# DE-010824.net
KiCad netlist of a schematic drawn in Altium Designer
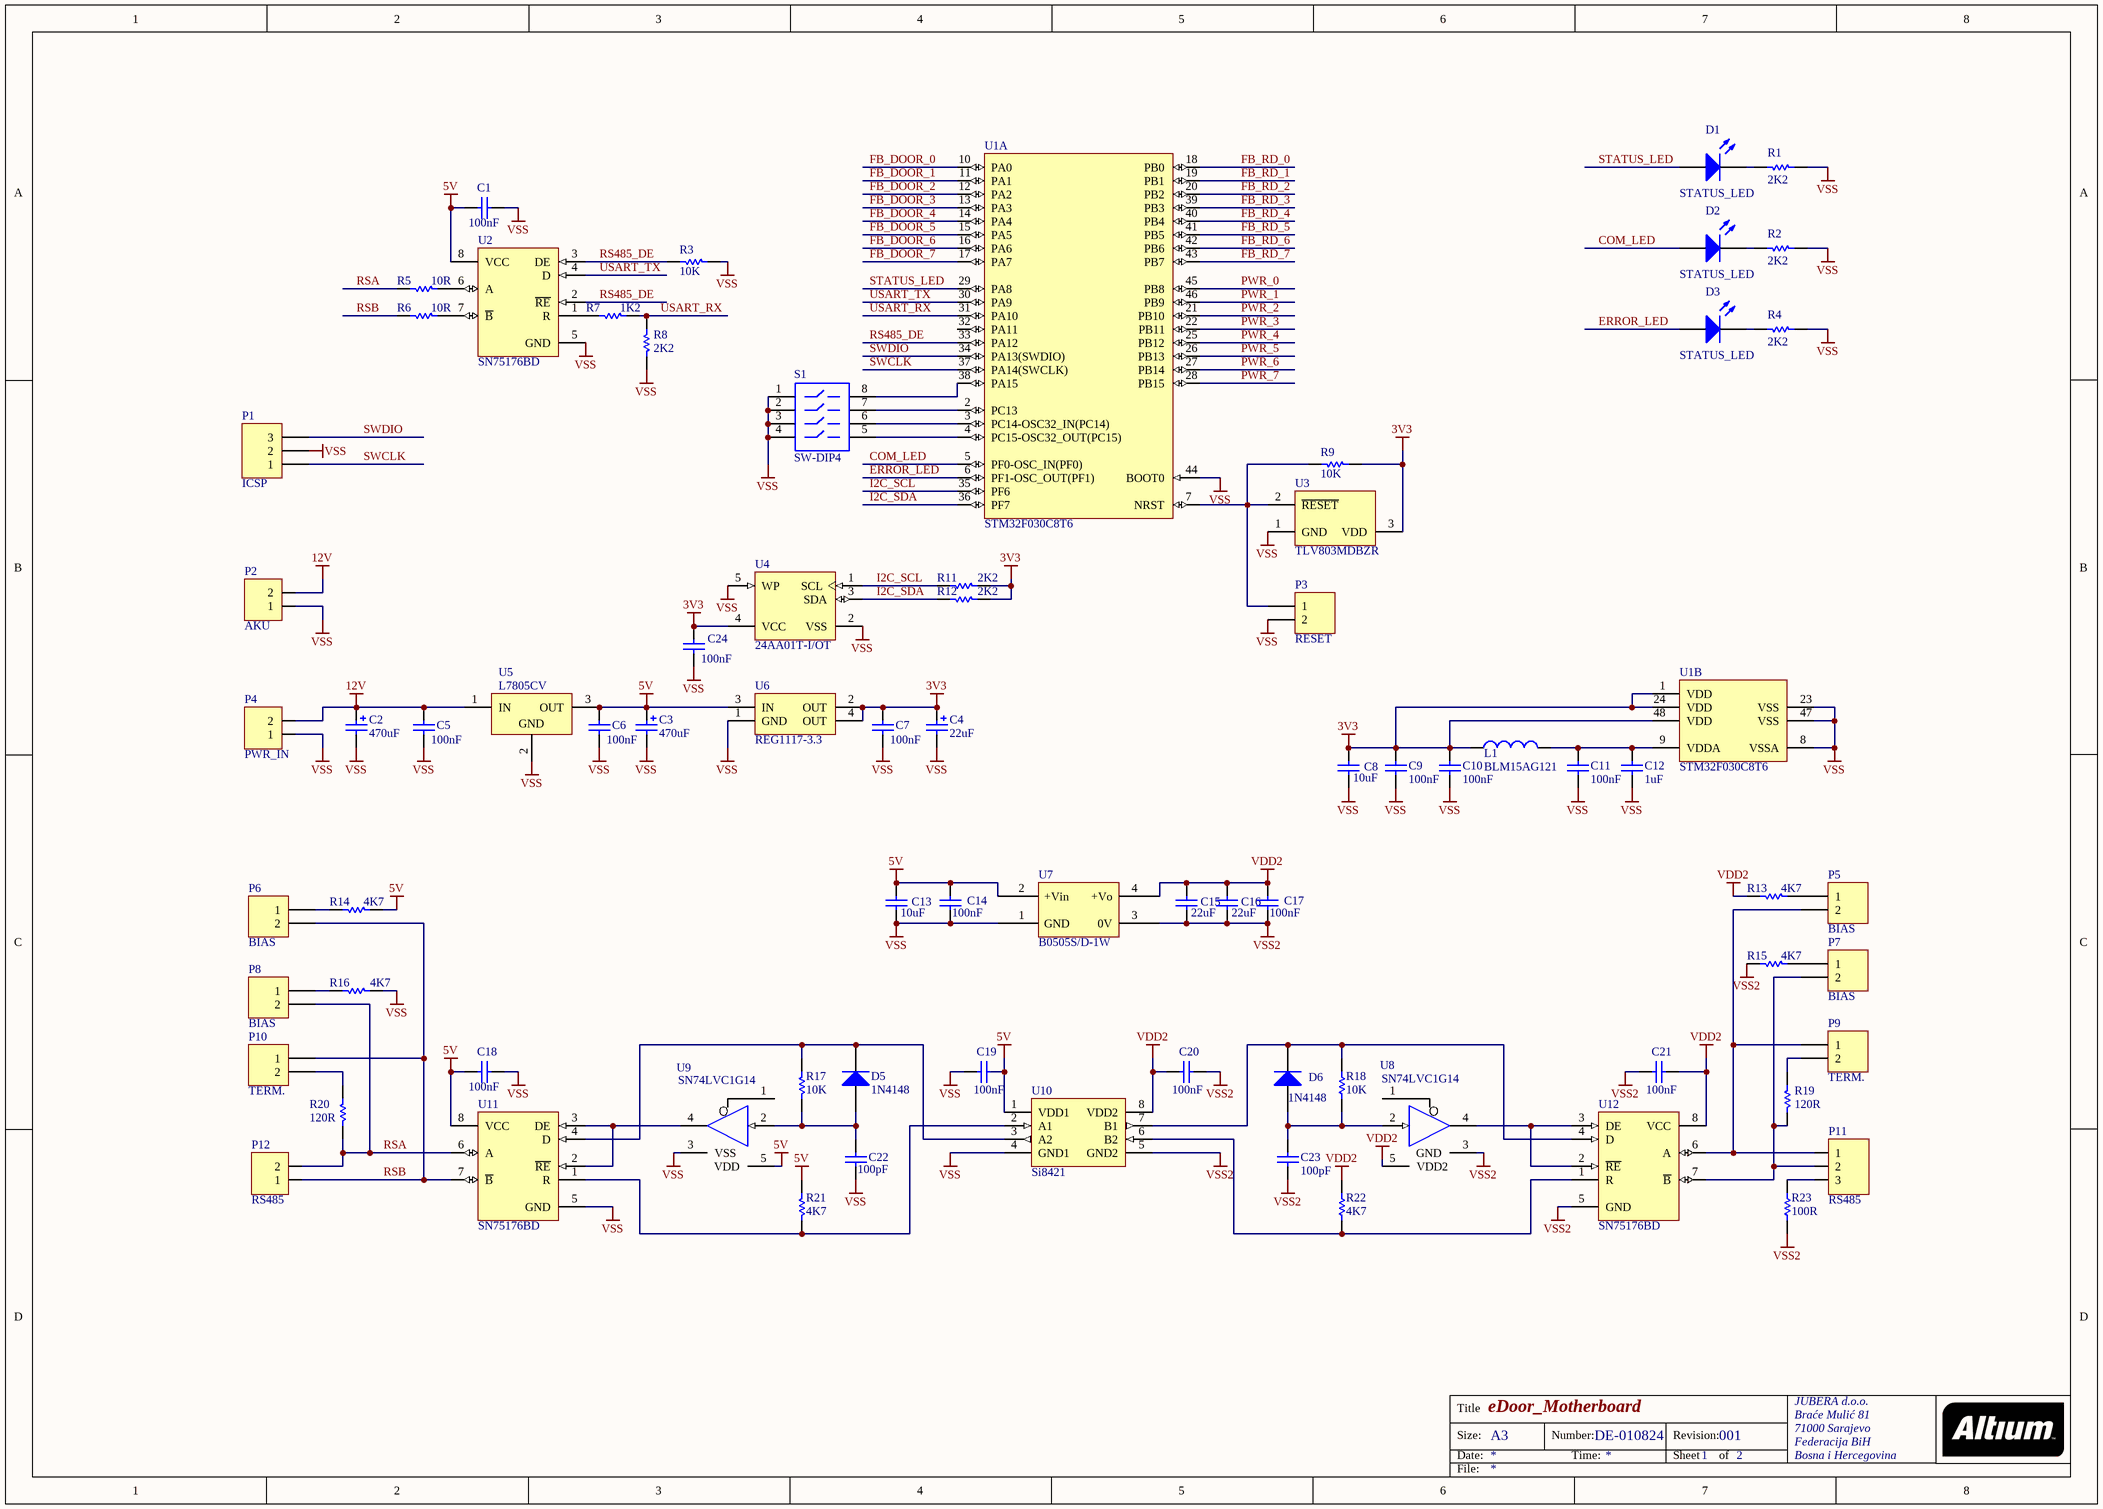
[diagram p0: DE-010824.SchDoc]

(export (version "E")
  (design (tool "Eeschema 10.0.6"))
  (components
    (comp (ref "C1")
      (value "100nF")
      (footprint "0603")
      (description "Ceramic Chip Capacitor - Standard")
      (fields (field (name "PUBLISHER") "Altium Limited"))
      (libsource (lib "DE-220817") (part "C0603"))
    )
    (comp (ref "C2")
      (value "470uF")
      (footprint "CAPPR5-10X12.5")
      (description "Aluminum Electrolytic Capacitor, Radial Style with Long Leads: 470uF, 25V")
      (fields (field (name "PUBLISHER") "Altium Limited"))
      (libsource (lib "DE-010824") (part "EKA00DC347E00"))
    )
    (comp (ref "C3")
      (value "470uF")
      (footprint "CAPPR5-10X12.5")
      (description "Aluminum Electrolytic Capacitor, Radial Style with Long Leads: 470uF, 25V")
      (fields (field (name "PUBLISHER") "Altium Limited"))
      (libsource (lib "DE-010824") (part "EKA00DC347E00"))
    )
    (comp (ref "C4")
      (value "22uF")
      (footprint "CAPPR2-5X11")
      (description "Aluminum Electrolytic Capacitor, Radial Style with Long Leads: 47uF, 35V")
      (fields (field (name "PUBLISHER") "Altium Limited"))
      (libsource (lib "DE-010824") (part "EKA00AA247F00"))
    )
    (comp (ref "C5")
      (value "100nF")
      (footprint "0603")
      (description "Ceramic Chip Capacitor - Standard")
      (fields (field (name "PUBLISHER") "Altium Limited"))
      (libsource (lib "DE-220817") (part "C0603"))
    )
    (comp (ref "C6")
      (value "100nF")
      (footprint "0603")
      (description "Ceramic Chip Capacitor - Standard")
      (fields (field (name "PUBLISHER") "Altium Limited"))
      (libsource (lib "DE-220817") (part "C0603"))
    )
    (comp (ref "C7")
      (value "100nF")
      (footprint "0603")
      (description "Ceramic Chip Capacitor - Standard")
      (fields (field (name "PUBLISHER") "Altium Limited"))
      (libsource (lib "DE-220817") (part "C0603"))
    )
    (comp (ref "C8")
      (value "10uF")
      (footprint "0805")
      (description "Ceramic Chip Capacitor - Standard")
      (fields (field (name "PUBLISHER") "Altium Limited"))
      (libsource (lib "DE-220817") (part "C0805"))
    )
    (comp (ref "C9")
      (value "100nF")
      (footprint "0603")
      (description "Ceramic Chip Capacitor - Standard")
      (fields (field (name "PUBLISHER") "Altium Limited"))
      (libsource (lib "DE-220817") (part "C0603"))
    )
    (comp (ref "C10")
      (value "100nF")
      (footprint "0603")
      (description "Ceramic Chip Capacitor - Standard")
      (fields (field (name "PUBLISHER") "Altium Limited"))
      (libsource (lib "DE-220817") (part "C0603"))
    )
    (comp (ref "C11")
      (value "100nF")
      (footprint "0603")
      (description "Ceramic Chip Capacitor - Standard")
      (fields (field (name "PUBLISHER") "Altium Limited"))
      (libsource (lib "DE-220817") (part "C0603"))
    )
    (comp (ref "C12")
      (value "1uF")
      (footprint "0603")
      (description "Ceramic Chip Capacitor - Standard")
      (fields (field (name "PUBLISHER") "Altium Limited"))
      (libsource (lib "DE-220817") (part "C0603"))
    )
    (comp (ref "C13")
      (value "10uF")
      (footprint "0805")
      (description "Ceramic Chip Capacitor - Standard")
      (fields (field (name "PUBLISHER") "Altium Limited"))
      (libsource (lib "DE-220817") (part "C0805"))
    )
    (comp (ref "C14")
      (value "100nF")
      (footprint "0603")
      (description "Ceramic Chip Capacitor - Standard")
      (fields (field (name "PUBLISHER") "Altium Limited"))
      (libsource (lib "DE-220817") (part "C0603"))
    )
    (comp (ref "C15")
      (value "22uF")
      (footprint "0805")
      (description "Ceramic Chip Capacitor - Standard")
      (fields (field (name "PUBLISHER") "Altium Limited"))
      (libsource (lib "DE-220817") (part "C0805"))
    )
    (comp (ref "C16")
      (value "22uF")
      (footprint "0805")
      (description "Ceramic Chip Capacitor - Standard")
      (fields (field (name "PUBLISHER") "Altium Limited"))
      (libsource (lib "DE-220817") (part "C0805"))
    )
    (comp (ref "C17")
      (value "100nF")
      (footprint "0603")
      (description "Ceramic Chip Capacitor - Standard")
      (fields (field (name "PUBLISHER") "Altium Limited"))
      (libsource (lib "DE-220817") (part "C0603"))
    )
    (comp (ref "C18")
      (value "100nF")
      (footprint "0603")
      (description "Ceramic Chip Capacitor - Standard")
      (fields (field (name "PUBLISHER") "Altium Limited"))
      (libsource (lib "DE-220817") (part "C0603"))
    )
    (comp (ref "C19")
      (value "100nF")
      (footprint "0603")
      (description "Ceramic Chip Capacitor - Standard")
      (fields (field (name "PUBLISHER") "Altium Limited"))
      (libsource (lib "DE-220817") (part "C0603"))
    )
    (comp (ref "C20")
      (value "100nF")
      (footprint "0603")
      (description "Ceramic Chip Capacitor - Standard")
      (fields (field (name "PUBLISHER") "Altium Limited"))
      (libsource (lib "DE-220817") (part "C0603"))
    )
    (comp (ref "C21")
      (value "100nF")
      (footprint "0603")
      (description "Ceramic Chip Capacitor - Standard")
      (fields (field (name "PUBLISHER") "Altium Limited"))
      (libsource (lib "DE-220817") (part "C0603"))
    )
    (comp (ref "C22")
      (value "100pF")
      (footprint "0603")
      (description "Ceramic Chip Capacitor - Standard")
      (fields (field (name "PUBLISHER") "Altium Limited"))
      (libsource (lib "DE-220817") (part "C0603"))
    )
    (comp (ref "C23")
      (value "100pF")
      (footprint "0603")
      (description "Ceramic Chip Capacitor - Standard")
      (fields (field (name "PUBLISHER") "Altium Limited"))
      (libsource (lib "DE-220817") (part "C0603"))
    )
    (comp (ref "C24")
      (value "100nF")
      (footprint "0603")
      (description "Ceramic Chip Capacitor - Standard")
      (fields (field (name "PUBLISHER") "Altium Limited"))
      (libsource (lib "DE-220817") (part "C0603"))
    )
    (comp (ref "D1")
      (value "STATUS_LED")
      (footprint "1.6X0.8X0.8")
      (description "Blue Surface Mount Chip LED, Blue")
      (fields (field (name "PUBLISHER") "Altium Limited"))
      (libsource (lib "DE-010824") (part "HSMB-C190"))
    )
    (comp (ref "D2")
      (value "STATUS_LED")
      (footprint "1.6X0.8X0.8")
      (description "Blue Surface Mount Chip LED, Blue")
      (fields (field (name "PUBLISHER") "Altium Limited"))
      (libsource (lib "DE-010824") (part "HSMB-C190"))
    )
    (comp (ref "D3")
      (value "STATUS_LED")
      (footprint "1.6X0.8X0.8")
      (description "Blue Surface Mount Chip LED, Blue")
      (fields (field (name "PUBLISHER") "Altium Limited"))
      (libsource (lib "DE-010824") (part "HSMB-C190"))
    )
    (comp (ref "D5")
      (value "1N4148")
      (footprint "SOD323")
      (description "General-purpose Diode")
      (fields (field (name "PUBLISHER") "Altium Limited"))
      (libsource (lib "Philips Discrete Diode - Switching") (part "BAS321"))
    )
    (comp (ref "D6")
      (value "1N4148")
      (footprint "SOD323")
      (description "General-purpose Diode")
      (fields (field (name "PUBLISHER") "Altium Limited"))
      (libsource (lib "Philips Discrete Diode - Switching") (part "BAS321"))
    )
    (comp (ref "L1")
      (value "BLM15AG121")
      (footprint "0603")
      (description "SMD chip inductor")
      (fields (field (name "PUBLISHER") "Altium Limited"))
      (libsource (lib "DE-010824") (part "Chip inductor"))
    )
    (comp (ref "P1")
      (value "ICSP")
      (footprint "HDR1X3")
      (description "Header, 3-Pin")
      (fields (field (name "PUBLISHER") "Altium Limited"))
      (libsource (lib "Miscellaneous Connectors") (part "Header 3"))
    )
    (comp (ref "P2")
      (value "AKU")
      (footprint "TERMINAL BLOK 2")
      (description "Terminal blok konektor 3,5 mm")
      (libsource (lib "DE-010824") (part "TERMINAL BLOK 2"))
    )
    (comp (ref "P3")
      (value "RESET")
      (footprint "HDR1X2")
      (description "Header, 2-Pin")
      (fields (field (name "PUBLISHER") "Altium Limited"))
      (libsource (lib "Miscellaneous Connectors") (part "Header 2"))
    )
    (comp (ref "P4")
      (value "PWR_IN")
      (footprint "TERMINAL BLOK 2")
      (description "Terminal blok konektor 3,5 mm")
      (libsource (lib "DE-010824") (part "TERMINAL BLOK 2"))
    )
    (comp (ref "P5")
      (value "BIAS")
      (footprint "HDR1X2")
      (description "Header, 2-Pin")
      (fields (field (name "PUBLISHER") "Altium Limited"))
      (libsource (lib "Miscellaneous Connectors") (part "Header 2"))
    )
    (comp (ref "P6")
      (value "BIAS")
      (footprint "HDR1X2")
      (description "Header, 2-Pin")
      (fields (field (name "PUBLISHER") "Altium Limited"))
      (libsource (lib "") (part "Header 2_1"))
    )
    (comp (ref "P7")
      (value "BIAS")
      (footprint "HDR1X2")
      (description "Header, 2-Pin")
      (fields (field (name "PUBLISHER") "Altium Limited"))
      (libsource (lib "Miscellaneous Connectors") (part "Header 2"))
    )
    (comp (ref "P8")
      (value "BIAS")
      (footprint "HDR1X2")
      (description "Header, 2-Pin")
      (fields (field (name "PUBLISHER") "Altium Limited"))
      (libsource (lib "") (part "Header 2_1"))
    )
    (comp (ref "P9")
      (value "TERM.")
      (footprint "HDR1X2")
      (description "Header, 2-Pin")
      (fields (field (name "PUBLISHER") "Altium Limited"))
      (libsource (lib "Miscellaneous Connectors") (part "Header 2"))
    )
    (comp (ref "P10")
      (value "TERM.")
      (footprint "HDR1X2")
      (description "Header, 2-Pin")
      (fields (field (name "PUBLISHER") "Altium Limited"))
      (libsource (lib "") (part "Header 2_1"))
    )
    (comp (ref "P11")
      (value "RS485")
      (footprint "TERMINAL BLOK 3")
      (description "3 pinski terminal blok konektor")
      (libsource (lib "DE-010824") (part "TERMINAL BLOK 3"))
    )
    (comp (ref "P12")
      (value "RS485")
      (footprint "TERMINAL BLOK 2")
      (description "Terminal blok konektor 3,5 mm")
      (libsource (lib "DE-010824") (part "TERMINAL BLOK 2"))
    )
    (comp (ref "R1")
      (value "2K2")
      (footprint "ERA-0603")
      (fields (field (name "PUBLISHER") "Altium Limited"))
      (libsource (lib "DE-220817") (part "ERAV"))
    )
    (comp (ref "R2")
      (value "2K2")
      (footprint "ERA-0603")
      (fields (field (name "PUBLISHER") "Altium Limited"))
      (libsource (lib "DE-220817") (part "ERAV"))
    )
    (comp (ref "R3")
      (value "10K")
      (footprint "ERA-0603")
      (fields (field (name "PUBLISHER") "Altium Limited"))
      (libsource (lib "DE-220817") (part "ERAV"))
    )
    (comp (ref "R4")
      (value "2K2")
      (footprint "ERA-0603")
      (fields (field (name "PUBLISHER") "Altium Limited"))
      (libsource (lib "DE-220817") (part "ERAV"))
    )
    (comp (ref "R5")
      (value "10R")
      (footprint "ERA-0603")
      (fields (field (name "PUBLISHER") "Altium Limited"))
      (libsource (lib "DE-220817") (part "ERAV"))
    )
    (comp (ref "R6")
      (value "10R")
      (footprint "ERA-0603")
      (fields (field (name "PUBLISHER") "Altium Limited"))
      (libsource (lib "DE-220817") (part "ERAV"))
    )
    (comp (ref "R7")
      (value "1K2")
      (footprint "ERA-0603")
      (fields (field (name "PUBLISHER") "Altium Limited"))
      (libsource (lib "DE-220817") (part "ERAV"))
    )
    (comp (ref "R8")
      (value "2K2")
      (footprint "ERA-0603")
      (fields (field (name "PUBLISHER") "Altium Limited"))
      (libsource (lib "DE-220817") (part "ERAV"))
    )
    (comp (ref "R9")
      (value "10K")
      (footprint "ERA-0603")
      (fields (field (name "PUBLISHER") "Altium Limited"))
      (libsource (lib "DE-220817") (part "ERAV"))
    )
    (comp (ref "R11")
      (value "2K2")
      (footprint "ERA-0603")
      (fields (field (name "PUBLISHER") "Altium Limited"))
      (libsource (lib "DE-220817") (part "ERAV"))
    )
    (comp (ref "R12")
      (value "2K2")
      (footprint "ERA-0603")
      (fields (field (name "PUBLISHER") "Altium Limited"))
      (libsource (lib "DE-220817") (part "ERAV"))
    )
    (comp (ref "R13")
      (value "4K7")
      (footprint "ERA-0603")
      (fields (field (name "PUBLISHER") "Altium Limited"))
      (libsource (lib "DE-220817") (part "ERAV"))
    )
    (comp (ref "R14")
      (value "4K7")
      (footprint "ERA-0603")
      (fields (field (name "PUBLISHER") "Altium Limited"))
      (libsource (lib "DE-220817") (part "ERAV"))
    )
    (comp (ref "R15")
      (value "4K7")
      (footprint "ERA-0603")
      (fields (field (name "PUBLISHER") "Altium Limited"))
      (libsource (lib "DE-220817") (part "ERAV"))
    )
    (comp (ref "R16")
      (value "4K7")
      (footprint "ERA-0603")
      (fields (field (name "PUBLISHER") "Altium Limited"))
      (libsource (lib "DE-220817") (part "ERAV"))
    )
    (comp (ref "R17")
      (value "10K")
      (footprint "ERA-0603")
      (fields (field (name "PUBLISHER") "Altium Limited"))
      (libsource (lib "DE-220817") (part "ERAV"))
    )
    (comp (ref "R18")
      (value "10K")
      (footprint "ERA-0603")
      (fields (field (name "PUBLISHER") "Altium Limited"))
      (libsource (lib "DE-220817") (part "ERAV"))
    )
    (comp (ref "R19")
      (value "120R")
      (footprint "ERA-0603")
      (fields (field (name "PUBLISHER") "Altium Limited"))
      (libsource (lib "DE-220817") (part "ERAV"))
    )
    (comp (ref "R20")
      (value "120R")
      (footprint "ERA-0603")
      (fields (field (name "PUBLISHER") "Altium Limited"))
      (libsource (lib "DE-220817") (part "ERAV"))
    )
    (comp (ref "R21")
      (value "4K7")
      (footprint "ERA-0603")
      (fields (field (name "PUBLISHER") "Altium Limited"))
      (libsource (lib "DE-220817") (part "ERAV"))
    )
    (comp (ref "R22")
      (value "4K7")
      (footprint "ERA-0603")
      (fields (field (name "PUBLISHER") "Altium Limited"))
      (libsource (lib "DE-220817") (part "ERAV"))
    )
    (comp (ref "R23")
      (value "100R")
      (footprint "ERA-0805")
      (fields (field (name "PUBLISHER") "Altium Limited"))
      (libsource (lib "DE-010824") (part "ERA6Y"))
    )
    (comp (ref "S1")
      (value "SW-DIP4")
      (footprint "DIP-8")
      (description "DIP Switch")
      (fields (field (name "PUBLISHER") "Altium Limited"))
      (libsource (lib "Miscellaneous Devices") (part "SW-DIP4"))
    )
    (comp (ref "U1")
      (value "STM32F030C8T6")
      (footprint "STM-LQFP48_N")
      (libsource (lib "STMicroelectronics STM32 F0") (part "STM32F030C8T6"))
    )
    (comp (ref "U2")
      (value "SN75176BD")
      (footprint "D008_N")
      (description "Differential Bus Transceiver")
      (fields (field (name "PUBLISHER") "Altium Limited"))
      (libsource (lib "DE-010824") (part "SN75176BD"))
    )
    (comp (ref "U3")
      (value "TLV803MDBZR")
      (footprint "DBZ3_N")
      (fields (field (name "MANUFACTURER") "Texas Instruments"))
      (libsource (lib "TI Power Management Supervisor and Reset IC") (part "TLV803MDBZR"))
    )
    (comp (ref "U4")
      (value "24AA01T-I/OT")
      (footprint "SOT-23-OT5_N")
      (description "1Kbit, 400kHz, 1.8V, I2C Serial EEPROM, 5-Pin SOT-23, Industrial Temperature, Tape and Reel")
      (fields (field (name "PUBLISHER") "Altium Limited"))
      (libsource (lib "Microchip Memory I2C Serial EEPROM") (part "24AA01T-I/OT"))
    )
    (comp (ref "U5")
      (value "L7805CV")
      (footprint "TO220")
      (description "Positive Voltage Regulator, 5V, 3-Pin TO-220")
      (libsource (lib "DE-010824") (part "L7805CV"))
    )
    (comp (ref "U6")
      (value "REG1117-3.3")
      (footprint "ZZ311")
      (description "800mA and 1A Low Dropout Positive Regulator 2.85V, 3.3V, 5V, and Adjustable")
      (fields (field (name "PUBLISHER") "Altium Limited"))
      (libsource (lib "DE-010824") (part "REG1117-3.3"))
    )
    (comp (ref "U7")
      (value "B0505S/D-1W")
      (footprint "B0505S-1W")
      (description "1W isolated dc dc converter")
      (libsource (lib "DE-220817") (part "B0505S/D"))
    )
    (comp (ref "U8")
      (value "SN74LVC1G14")
      (footprint "419A-01_N")
      (description "Non-Inverting 3-State Buffer")
      (fields (field (name "PUBLISHER") "Altium Limited"))
      (libsource (lib "ON Semi Logic Buffer Line Driver") (part "MC74VHC1G125DFT1"))
    )
    (comp (ref "U9")
      (value "SN74LVC1G14")
      (footprint "419A-01_N")
      (description "Non-Inverting 3-State Buffer")
      (fields (field (name "PUBLISHER") "Altium Limited"))
      (libsource (lib "ON Semi Logic Buffer Line Driver") (part "MC74VHC1G125DFT1"))
    )
    (comp (ref "U10")
      (value "Si8421")
      (footprint "SOP8")
      (description "Silicon Labs low power dual chanel digital isolator")
      (libsource (lib "DE-010824") (part "Si8421"))
    )
    (comp (ref "U11")
      (value "SN75176BD")
      (footprint "D008_N")
      (description "Differential Bus Transceiver")
      (fields (field (name "PUBLISHER") "Altium Limited"))
      (libsource (lib "") (part "SN75176BD_1"))
    )
    (comp (ref "U12")
      (value "SN75176BD")
      (footprint "D008_N")
      (description "Differential Bus Transceiver")
      (fields (field (name "PUBLISHER") "Altium Limited"))
      (libsource (lib "DE-220817") (part "SN75176BD"))
    )
  )
  (nets
    (net (code "1") (name "/COM_LED") (class "Default")
      (node (ref "D2") (pin "1") (pinfunction "A_1") (pintype "passive"))
      (node (ref "U1") (pin "5") (pinfunction "PF0-OSC_IN(PF0)_5") (pintype "bidirectional"))
    )
    (net (code "2") (name "/ERROR_LED") (class "Default")
      (node (ref "D3") (pin "1") (pinfunction "A_1") (pintype "passive"))
      (node (ref "U1") (pin "6") (pinfunction "PF1-OSC_OUT(PF1)_6") (pintype "bidirectional"))
    )
    (net (code "3") (name "/FB_DOOR_0") (class "Default")
      (node (ref "U1") (pin "10") (pinfunction "PA0_10") (pintype "bidirectional"))
    )
    (net (code "4") (name "/FB_DOOR_1") (class "Default")
      (node (ref "U1") (pin "11") (pinfunction "PA1_11") (pintype "bidirectional"))
    )
    (net (code "5") (name "/FB_DOOR_2") (class "Default")
      (node (ref "U1") (pin "12") (pinfunction "PA2_12") (pintype "bidirectional"))
    )
    (net (code "6") (name "/FB_DOOR_3") (class "Default")
      (node (ref "U1") (pin "13") (pinfunction "PA3_13") (pintype "bidirectional"))
    )
    (net (code "7") (name "/FB_DOOR_4") (class "Default")
      (node (ref "U1") (pin "14") (pinfunction "PA4_14") (pintype "bidirectional"))
    )
    (net (code "8") (name "/FB_DOOR_5") (class "Default")
      (node (ref "U1") (pin "15") (pinfunction "PA5_15") (pintype "bidirectional"))
    )
    (net (code "9") (name "/FB_DOOR_6") (class "Default")
      (node (ref "U1") (pin "16") (pinfunction "PA6_16") (pintype "bidirectional"))
    )
    (net (code "10") (name "/FB_DOOR_7") (class "Default")
      (node (ref "U1") (pin "17") (pinfunction "PA7_17") (pintype "bidirectional"))
    )
    (net (code "11") (name "/FB_RD_0") (class "Default")
      (node (ref "U1") (pin "18") (pinfunction "PB0_18") (pintype "bidirectional"))
    )
    (net (code "12") (name "/FB_RD_1") (class "Default")
      (node (ref "U1") (pin "19") (pinfunction "PB1_19") (pintype "bidirectional"))
    )
    (net (code "13") (name "/FB_RD_2") (class "Default")
      (node (ref "U1") (pin "20") (pinfunction "PB2_20") (pintype "bidirectional"))
    )
    (net (code "14") (name "/FB_RD_3") (class "Default")
      (node (ref "U1") (pin "39") (pinfunction "PB3_39") (pintype "bidirectional"))
    )
    (net (code "15") (name "/FB_RD_4") (class "Default")
      (node (ref "U1") (pin "40") (pinfunction "PB4_40") (pintype "bidirectional"))
    )
    (net (code "16") (name "/FB_RD_5") (class "Default")
      (node (ref "U1") (pin "41") (pinfunction "PB5_41") (pintype "bidirectional"))
    )
    (net (code "17") (name "/FB_RD_6") (class "Default")
      (node (ref "U1") (pin "42") (pinfunction "PB6_42") (pintype "bidirectional"))
    )
    (net (code "18") (name "/FB_RD_7") (class "Default")
      (node (ref "U1") (pin "43") (pinfunction "PB7_43") (pintype "bidirectional"))
    )
    (net (code "19") (name "/I2C_SCL") (class "Default")
      (node (ref "R11") (pin "1") (pinfunction "1_1") (pintype "passive"))
      (node (ref "U1") (pin "35") (pinfunction "PF6_35") (pintype "bidirectional"))
      (node (ref "U4") (pin "1") (pinfunction "SCL_1") (pintype "input"))
    )
    (net (code "20") (name "/I2C_SDA") (class "Default")
      (node (ref "R12") (pin "1") (pinfunction "1_1") (pintype "passive"))
      (node (ref "U1") (pin "36") (pinfunction "PF7_36") (pintype "bidirectional"))
      (node (ref "U4") (pin "3") (pinfunction "SDA_3") (pintype "bidirectional"))
    )
    (net (code "21") (name "/PWR_0") (class "Default")
      (node (ref "U1") (pin "45") (pinfunction "PB8_45") (pintype "bidirectional"))
    )
    (net (code "22") (name "/PWR_1") (class "Default")
      (node (ref "U1") (pin "46") (pinfunction "PB9_46") (pintype "bidirectional"))
    )
    (net (code "23") (name "/PWR_2") (class "Default")
      (node (ref "U1") (pin "21") (pinfunction "PB10_21") (pintype "bidirectional"))
    )
    (net (code "24") (name "/PWR_3") (class "Default")
      (node (ref "U1") (pin "22") (pinfunction "PB11_22") (pintype "bidirectional"))
    )
    (net (code "25") (name "/PWR_4") (class "Default")
      (node (ref "U1") (pin "25") (pinfunction "PB12_25") (pintype "bidirectional"))
    )
    (net (code "26") (name "/PWR_5") (class "Default")
      (node (ref "U1") (pin "26") (pinfunction "PB13_26") (pintype "bidirectional"))
    )
    (net (code "27") (name "/PWR_6") (class "Default")
      (node (ref "U1") (pin "27") (pinfunction "PB14_27") (pintype "bidirectional"))
    )
    (net (code "28") (name "/PWR_7") (class "Default")
      (node (ref "U1") (pin "28") (pinfunction "PB15_28") (pintype "bidirectional"))
    )
    (net (code "29") (name "/RS485_DE") (class "Default")
      (node (ref "R3") (pin "2") (pinfunction "2_2") (pintype "passive"))
      (node (ref "U1") (pin "33") (pinfunction "PA12_33") (pintype "bidirectional"))
      (node (ref "U2") (pin "2") (pinfunction "~{RE}_2") (pintype "input"))
      (node (ref "U2") (pin "3") (pinfunction "DE_3") (pintype "input"))
    )
    (net (code "30") (name "/RSA") (class "Default")
      (node (ref "P12") (pin "2") (pinfunction "2_2") (pintype "passive"))
      (node (ref "P8") (pin "2") (pinfunction "2_2") (pintype "passive"))
      (node (ref "R20") (pin "1") (pinfunction "1_1") (pintype "passive"))
      (node (ref "R5") (pin "1") (pinfunction "1_1") (pintype "passive"))
      (node (ref "U11") (pin "6") (pinfunction "A_6") (pintype "bidirectional"))
    )
    (net (code "31") (name "/RSB") (class "Default")
      (node (ref "P10") (pin "1") (pinfunction "1_1") (pintype "passive"))
      (node (ref "P12") (pin "1") (pinfunction "1_1") (pintype "passive"))
      (node (ref "P6") (pin "2") (pinfunction "2_2") (pintype "passive"))
      (node (ref "R6") (pin "1") (pinfunction "1_1") (pintype "passive"))
      (node (ref "U11") (pin "7") (pinfunction "~{B}_7") (pintype "bidirectional"))
    )
    (net (code "32") (name "/STATUS_LED") (class "Default")
      (node (ref "D1") (pin "1") (pinfunction "A_1") (pintype "passive"))
      (node (ref "U1") (pin "29") (pinfunction "PA8_29") (pintype "bidirectional"))
    )
    (net (code "33") (name "/SWCLK") (class "Default")
      (node (ref "P1") (pin "1") (pinfunction "1_1") (pintype "passive"))
      (node (ref "U1") (pin "37") (pinfunction "PA14(SWCLK)_37") (pintype "bidirectional"))
    )
    (net (code "34") (name "/SWDIO") (class "Default")
      (node (ref "P1") (pin "3") (pinfunction "3_3") (pintype "passive"))
      (node (ref "U1") (pin "34") (pinfunction "PA13(SWDIO)_34") (pintype "bidirectional"))
    )
    (net (code "35") (name "/USART_RX") (class "Default")
      (node (ref "R7") (pin "1") (pinfunction "1_1") (pintype "passive"))
      (node (ref "R8") (pin "1") (pinfunction "1_1") (pintype "passive"))
      (node (ref "U1") (pin "31") (pinfunction "PA10_31") (pintype "bidirectional"))
    )
    (net (code "36") (name "/USART_TX") (class "Default")
      (node (ref "U1") (pin "30") (pinfunction "PA9_30") (pintype "bidirectional"))
      (node (ref "U2") (pin "4") (pinfunction "D_4") (pintype "input"))
    )
    (net (code "37") (name "3V3") (class "Default")
      (node (ref "C10") (pin "1") (pinfunction "1_1") (pintype "passive"))
      (node (ref "C24") (pin "2") (pinfunction "2_2") (pintype "passive"))
      (node (ref "C4") (pin "1") (pinfunction "1_1") (pintype "passive"))
      (node (ref "C7") (pin "2") (pinfunction "2_2") (pintype "passive"))
      (node (ref "C8") (pin "2") (pinfunction "2_2") (pintype "passive"))
      (node (ref "C9") (pin "1") (pinfunction "1_1") (pintype "passive"))
      (node (ref "L1") (pin "1") (pinfunction "1_1") (pintype "passive"))
      (node (ref "R11") (pin "2") (pinfunction "2_2") (pintype "passive"))
      (node (ref "R12") (pin "2") (pinfunction "2_2") (pintype "passive"))
      (node (ref "R9") (pin "2") (pinfunction "2_2") (pintype "passive"))
      (node (ref "U1") (pin "1") (pinfunction "VDD_1") (pintype "power_in"))
      (node (ref "U1") (pin "24") (pinfunction "VDD_24") (pintype "power_in"))
      (node (ref "U1") (pin "48") (pinfunction "VDD_48") (pintype "power_in"))
      (node (ref "U3") (pin "3") (pinfunction "VDD_3") (pintype "power_in"))
      (node (ref "U4") (pin "4") (pinfunction "VCC_4") (pintype "power_in"))
      (node (ref "U6") (pin "2") (pinfunction "OUT_2") (pintype "power_in"))
      (node (ref "U6") (pin "4") (pinfunction "OUT_4") (pintype "power_in"))
    )
    (net (code "38") (name "5V") (class "Default")
      (node (ref "C1") (pin "1") (pinfunction "1_1") (pintype "passive"))
      (node (ref "C13") (pin "2") (pinfunction "2_2") (pintype "passive"))
      (node (ref "C14") (pin "2") (pinfunction "2_2") (pintype "passive"))
      (node (ref "C15") (pin "2") (pinfunction "2_2") (pintype "passive"))
      (node (ref "C16") (pin "2") (pinfunction "2_2") (pintype "passive"))
      (node (ref "C17") (pin "2") (pinfunction "2_2") (pintype "passive"))
      (node (ref "C18") (pin "1") (pinfunction "1_1") (pintype "passive"))
      (node (ref "C19") (pin "2") (pinfunction "2_2") (pintype "passive"))
      (node (ref "C20") (pin "2") (pinfunction "2_2") (pintype "passive"))
      (node (ref "C21") (pin "1") (pinfunction "1_1") (pintype "passive"))
      (node (ref "C3") (pin "1") (pinfunction "1_1") (pintype "passive"))
      (node (ref "C6") (pin "2") (pinfunction "2_2") (pintype "passive"))
      (node (ref "R13") (pin "2") (pinfunction "2_2") (pintype "passive"))
      (node (ref "R14") (pin "2") (pinfunction "2_2") (pintype "passive"))
      (node (ref "R21") (pin "2") (pinfunction "2_2") (pintype "passive"))
      (node (ref "R22") (pin "2") (pinfunction "2_2") (pintype "passive"))
      (node (ref "U10") (pin "1") (pinfunction "VDD1_1") (pintype "power_in"))
      (node (ref "U10") (pin "8") (pinfunction "VDD2_8") (pintype "power_in"))
      (node (ref "U11") (pin "8") (pinfunction "VCC_8") (pintype "power_in"))
      (node (ref "U12") (pin "8") (pinfunction "VCC_8") (pintype "power_in"))
      (node (ref "U2") (pin "8") (pinfunction "VCC_8") (pintype "power_in"))
      (node (ref "U5") (pin "3") (pinfunction "OUT_3") (pintype "power_in"))
      (node (ref "U6") (pin "3") (pinfunction "IN_3") (pintype "power_in"))
      (node (ref "U7") (pin "2") (pinfunction "+Vin_2") (pintype "passive"))
      (node (ref "U7") (pin "4") (pinfunction "+Vo_4") (pintype "passive"))
      (node (ref "U8") (pin "5") (pinfunction "VDD2_5") (pintype "power_in"))
      (node (ref "U9") (pin "5") (pinfunction "VDD2_5") (pintype "power_in"))
    )
    (net (code "39") (name "12V") (class "Default")
      (node (ref "C2") (pin "1") (pinfunction "1_1") (pintype "passive"))
      (node (ref "C5") (pin "2") (pinfunction "2_2") (pintype "passive"))
      (node (ref "P2") (pin "2") (pinfunction "2_2") (pintype "passive"))
      (node (ref "P4") (pin "2") (pinfunction "2_2") (pintype "passive"))
      (node (ref "U5") (pin "1") (pinfunction "IN_1") (pintype "power_in"))
    )
    (net (code "40") (name "Net-(D1-K)") (class "Default")
      (node (ref "D1") (pin "2") (pinfunction "K_2") (pintype "passive"))
      (node (ref "R1") (pin "2") (pinfunction "2_2") (pintype "passive"))
    )
    (net (code "41") (name "Net-(D2-K)") (class "Default")
      (node (ref "D2") (pin "2") (pinfunction "K_2") (pintype "passive"))
      (node (ref "R2") (pin "2") (pinfunction "2_2") (pintype "passive"))
    )
    (net (code "42") (name "Net-(D3-K)") (class "Default")
      (node (ref "D3") (pin "2") (pinfunction "K_2") (pintype "passive"))
      (node (ref "R4") (pin "2") (pinfunction "2_2") (pintype "passive"))
    )
    (net (code "43") (name "Net-(D5-A)") (class "Default")
      (node (ref "C22") (pin "2") (pinfunction "2_2") (pintype "passive"))
      (node (ref "D5") (pin "2") (pinfunction "A_2") (pintype "passive"))
      (node (ref "R17") (pin "1") (pinfunction "1_1") (pintype "passive"))
      (node (ref "U9") (pin "2") (pinfunction "A_2") (pintype "input"))
    )
    (net (code "44") (name "Net-(D5-K)") (class "Default")
      (node (ref "D5") (pin "1") (pinfunction "K_1") (pintype "passive"))
      (node (ref "R17") (pin "2") (pinfunction "2_2") (pintype "passive"))
      (node (ref "U10") (pin "3") (pinfunction "A2_3") (pintype "output"))
      (node (ref "U11") (pin "4") (pinfunction "D_4") (pintype "input"))
    )
    (net (code "45") (name "Net-(D6-A)") (class "Default")
      (node (ref "C23") (pin "2") (pinfunction "2_2") (pintype "passive"))
      (node (ref "D6") (pin "2") (pinfunction "A_2") (pintype "passive"))
      (node (ref "R18") (pin "1") (pinfunction "1_1") (pintype "passive"))
      (node (ref "U8") (pin "2") (pinfunction "A_2") (pintype "input"))
    )
    (net (code "46") (name "Net-(D6-K)") (class "Default")
      (node (ref "D6") (pin "1") (pinfunction "K_1") (pintype "passive"))
      (node (ref "R18") (pin "2") (pinfunction "2_2") (pintype "passive"))
      (node (ref "U10") (pin "7") (pinfunction "B1_7") (pintype "output"))
      (node (ref "U12") (pin "4") (pinfunction "D_4") (pintype "input"))
    )
    (net (code "47") (name "Net-(P5-Pad1)") (class "Default")
      (node (ref "P5") (pin "1") (pinfunction "1_1") (pintype "passive"))
      (node (ref "R13") (pin "1") (pinfunction "1_1") (pintype "passive"))
    )
    (net (code "48") (name "Net-(P6-Pad1)") (class "Default")
      (node (ref "P6") (pin "1") (pinfunction "1_1") (pintype "passive"))
      (node (ref "R14") (pin "1") (pinfunction "1_1") (pintype "passive"))
    )
    (net (code "49") (name "Net-(P7-Pad1)") (class "Default")
      (node (ref "P7") (pin "1") (pinfunction "1_1") (pintype "passive"))
      (node (ref "R15") (pin "1") (pinfunction "1_1") (pintype "passive"))
    )
    (net (code "50") (name "Net-(P8-Pad1)") (class "Default")
      (node (ref "P8") (pin "1") (pinfunction "1_1") (pintype "passive"))
      (node (ref "R16") (pin "1") (pinfunction "1_1") (pintype "passive"))
    )
    (net (code "51") (name "Net-(P9-Pad2)") (class "Default")
      (node (ref "P9") (pin "2") (pinfunction "2_2") (pintype "passive"))
      (node (ref "R19") (pin "2") (pinfunction "2_2") (pintype "passive"))
    )
    (net (code "52") (name "Net-(P10-Pad2)") (class "Default")
      (node (ref "P10") (pin "2") (pinfunction "2_2") (pintype "passive"))
      (node (ref "R20") (pin "2") (pinfunction "2_2") (pintype "passive"))
    )
    (net (code "53") (name "Net-(P11-Pad3)") (class "Default")
      (node (ref "P11") (pin "3") (pinfunction "3_3") (pintype "passive"))
      (node (ref "R23") (pin "2") (pinfunction "2_2") (pintype "passive"))
    )
    (net (code "54") (name "Net-(U1A-NRST)") (class "Default")
      (node (ref "P3") (pin "1") (pinfunction "1_1") (pintype "passive"))
      (node (ref "R9") (pin "1") (pinfunction "1_1") (pintype "passive"))
      (node (ref "U1") (pin "7") (pinfunction "NRST_7") (pintype "bidirectional"))
      (node (ref "U3") (pin "2") (pinfunction "~{RESET}_2") (pintype "open_collector"))
    )
    (net (code "55") (name "Net-(U1A-PA15)") (class "Default")
      (node (ref "S1") (pin "8") (pinfunction "8_8") (pintype "passive"))
      (node (ref "U1") (pin "38") (pinfunction "PA15_38") (pintype "bidirectional"))
    )
    (net (code "56") (name "Net-(U1A-PC13)") (class "Default")
      (node (ref "S1") (pin "7") (pinfunction "7_7") (pintype "passive"))
      (node (ref "U1") (pin "2") (pinfunction "PC13_2") (pintype "bidirectional"))
    )
    (net (code "57") (name "Net-(U1A-PC14-OSC32_IN(PC14))") (class "Default")
      (node (ref "S1") (pin "6") (pinfunction "6_6") (pintype "passive"))
      (node (ref "U1") (pin "3") (pinfunction "PC14-OSC32_IN(PC14)_3") (pintype "bidirectional"))
    )
    (net (code "58") (name "Net-(U1A-PC15-OSC32_OUT(PC15))") (class "Default")
      (node (ref "S1") (pin "5") (pinfunction "5_5") (pintype "passive"))
      (node (ref "U1") (pin "4") (pinfunction "PC15-OSC32_OUT(PC15)_4") (pintype "bidirectional"))
    )
    (net (code "59") (name "Net-(U1B-VDDA)") (class "Default")
      (node (ref "C11") (pin "1") (pinfunction "1_1") (pintype "passive"))
      (node (ref "C12") (pin "1") (pinfunction "1_1") (pintype "passive"))
      (node (ref "L1") (pin "2") (pinfunction "2_2") (pintype "passive"))
      (node (ref "U1") (pin "9") (pinfunction "VDDA_9") (pintype "power_in"))
    )
    (net (code "60") (name "Net-(U2-A)") (class "Default")
      (node (ref "R5") (pin "2") (pinfunction "2_2") (pintype "passive"))
      (node (ref "U2") (pin "6") (pinfunction "A_6") (pintype "bidirectional"))
    )
    (net (code "61") (name "Net-(U2-R)") (class "Default")
      (node (ref "R7") (pin "2") (pinfunction "2_2") (pintype "passive"))
      (node (ref "U2") (pin "1") (pinfunction "R_1") (pintype "tri_state"))
    )
    (net (code "62") (name "Net-(U2-~{B})") (class "Default")
      (node (ref "R6") (pin "2") (pinfunction "2_2") (pintype "passive"))
      (node (ref "U2") (pin "7") (pinfunction "~{B}_7") (pintype "bidirectional"))
    )
    (net (code "63") (name "Net-(U10-A1)") (class "Default")
      (node (ref "R21") (pin "1") (pinfunction "1_1") (pintype "passive"))
      (node (ref "U10") (pin "2") (pinfunction "A1_2") (pintype "input"))
      (node (ref "U11") (pin "1") (pinfunction "R_1") (pintype "tri_state"))
    )
    (net (code "64") (name "Net-(U10-B2)") (class "Default")
      (node (ref "R22") (pin "1") (pinfunction "1_1") (pintype "passive"))
      (node (ref "U10") (pin "6") (pinfunction "B2_6") (pintype "input"))
      (node (ref "U12") (pin "1") (pinfunction "R_1") (pintype "tri_state"))
    )
    (net (code "65") (name "Net-(U11-DE)") (class "Default")
      (node (ref "U11") (pin "2") (pinfunction "~{RE}_2") (pintype "input"))
      (node (ref "U11") (pin "3") (pinfunction "DE_3") (pintype "input"))
      (node (ref "U9") (pin "4") (pinfunction "Y_4") (pintype "tri_state"))
    )
    (net (code "66") (name "Net-(U12-A)") (class "Default")
      (node (ref "P11") (pin "1") (pinfunction "1_1") (pintype "passive"))
      (node (ref "P5") (pin "2") (pinfunction "2_2") (pintype "passive"))
      (node (ref "P9") (pin "1") (pinfunction "1_1") (pintype "passive"))
      (node (ref "U12") (pin "6") (pinfunction "A_6") (pintype "bidirectional"))
    )
    (net (code "67") (name "Net-(U12-DE)") (class "Default")
      (node (ref "U12") (pin "2") (pinfunction "~{RE}_2") (pintype "input"))
      (node (ref "U12") (pin "3") (pinfunction "DE_3") (pintype "input"))
      (node (ref "U8") (pin "4") (pinfunction "Y_4") (pintype "tri_state"))
    )
    (net (code "68") (name "Net-(U12-~{B})") (class "Default")
      (node (ref "P11") (pin "2") (pinfunction "2_2") (pintype "passive"))
      (node (ref "P7") (pin "2") (pinfunction "2_2") (pintype "passive"))
      (node (ref "R19") (pin "1") (pinfunction "1_1") (pintype "passive"))
      (node (ref "U12") (pin "7") (pinfunction "~{B}_7") (pintype "bidirectional"))
    )
    (net (code "69") (name "VSS") (class "Default")
      (node (ref "C1") (pin "2") (pinfunction "2_2") (pintype "passive"))
      (node (ref "C10") (pin "2") (pinfunction "2_2") (pintype "passive"))
      (node (ref "C11") (pin "2") (pinfunction "2_2") (pintype "passive"))
      (node (ref "C12") (pin "2") (pinfunction "2_2") (pintype "passive"))
      (node (ref "C13") (pin "1") (pinfunction "1_1") (pintype "passive"))
      (node (ref "C14") (pin "1") (pinfunction "1_1") (pintype "passive"))
      (node (ref "C15") (pin "1") (pinfunction "1_1") (pintype "passive"))
      (node (ref "C16") (pin "1") (pinfunction "1_1") (pintype "passive"))
      (node (ref "C17") (pin "1") (pinfunction "1_1") (pintype "passive"))
      (node (ref "C18") (pin "2") (pinfunction "2_2") (pintype "passive"))
      (node (ref "C19") (pin "1") (pinfunction "1_1") (pintype "passive"))
      (node (ref "C2") (pin "2") (pinfunction "2_2") (pintype "passive"))
      (node (ref "C20") (pin "1") (pinfunction "1_1") (pintype "passive"))
      (node (ref "C21") (pin "2") (pinfunction "2_2") (pintype "passive"))
      (node (ref "C22") (pin "1") (pinfunction "1_1") (pintype "passive"))
      (node (ref "C23") (pin "1") (pinfunction "1_1") (pintype "passive"))
      (node (ref "C24") (pin "1") (pinfunction "1_1") (pintype "passive"))
      (node (ref "C3") (pin "2") (pinfunction "2_2") (pintype "passive"))
      (node (ref "C4") (pin "2") (pinfunction "2_2") (pintype "passive"))
      (node (ref "C5") (pin "1") (pinfunction "1_1") (pintype "passive"))
      (node (ref "C6") (pin "1") (pinfunction "1_1") (pintype "passive"))
      (node (ref "C7") (pin "1") (pinfunction "1_1") (pintype "passive"))
      (node (ref "C8") (pin "1") (pinfunction "1_1") (pintype "passive"))
      (node (ref "C9") (pin "2") (pinfunction "2_2") (pintype "passive"))
      (node (ref "P1") (pin "2") (pinfunction "2_2") (pintype "passive"))
      (node (ref "P2") (pin "1") (pinfunction "1_1") (pintype "passive"))
      (node (ref "P3") (pin "2") (pinfunction "2_2") (pintype "passive"))
      (node (ref "P4") (pin "1") (pinfunction "1_1") (pintype "passive"))
      (node (ref "R1") (pin "1") (pinfunction "1_1") (pintype "passive"))
      (node (ref "R15") (pin "2") (pinfunction "2_2") (pintype "passive"))
      (node (ref "R16") (pin "2") (pinfunction "2_2") (pintype "passive"))
      (node (ref "R2") (pin "1") (pinfunction "1_1") (pintype "passive"))
      (node (ref "R23") (pin "1") (pinfunction "1_1") (pintype "passive"))
      (node (ref "R3") (pin "1") (pinfunction "1_1") (pintype "passive"))
      (node (ref "R4") (pin "1") (pinfunction "1_1") (pintype "passive"))
      (node (ref "R8") (pin "2") (pinfunction "2_2") (pintype "passive"))
      (node (ref "S1") (pin "1") (pinfunction "1_1") (pintype "passive"))
      (node (ref "S1") (pin "2") (pinfunction "2_2") (pintype "passive"))
      (node (ref "S1") (pin "3") (pinfunction "3_3") (pintype "passive"))
      (node (ref "S1") (pin "4") (pinfunction "4_4") (pintype "passive"))
      (node (ref "U1") (pin "23") (pinfunction "VSS_23") (pintype "power_in"))
      (node (ref "U1") (pin "44") (pinfunction "BOOT0_44") (pintype "input"))
      (node (ref "U1") (pin "47") (pinfunction "VSS_47") (pintype "power_in"))
      (node (ref "U1") (pin "8") (pinfunction "VSSA_8") (pintype "power_in"))
      (node (ref "U10") (pin "4") (pinfunction "GND1_4") (pintype "power_in"))
      (node (ref "U10") (pin "5") (pinfunction "GND2_5") (pintype "power_in"))
      (node (ref "U11") (pin "5") (pinfunction "GND_5") (pintype "power_in"))
      (node (ref "U12") (pin "5") (pinfunction "GND_5") (pintype "power_in"))
      (node (ref "U2") (pin "5") (pinfunction "GND_5") (pintype "power_in"))
      (node (ref "U3") (pin "1") (pinfunction "GND_1") (pintype "power_in"))
      (node (ref "U4") (pin "2") (pinfunction "VSS_2") (pintype "power_in"))
      (node (ref "U4") (pin "5") (pinfunction "WP_5") (pintype "input"))
      (node (ref "U5") (pin "2") (pinfunction "GND_2") (pintype "power_in"))
      (node (ref "U6") (pin "1") (pinfunction "GND_1") (pintype "power_in"))
      (node (ref "U7") (pin "1") (pinfunction "GND_1") (pintype "passive"))
      (node (ref "U7") (pin "3") (pinfunction "0V_3") (pintype "passive"))
      (node (ref "U8") (pin "3") (pinfunction "GND_3") (pintype "power_in"))
      (node (ref "U9") (pin "3") (pinfunction "GND_3") (pintype "power_in"))
    )
    (net (code "70") (name "unconnected-(U1A-PA11-Pad32)") (class "Default")
      (node (ref "U1") (pin "32") (pinfunction "PA11_32") (pintype "bidirectional"))
    )
    (net (code "71") (name "unconnected-(U8-NC-Pad1)") (class "Default")
      (node (ref "U8") (pin "1") (pinfunction "NC_1") (pintype "passive"))
    )
    (net (code "72") (name "unconnected-(U9-NC-Pad1)") (class "Default")
      (node (ref "U9") (pin "1") (pinfunction "NC_1") (pintype "passive"))
    )
  )
)
